# power_supply_v1.net
KiCad netlist of a schematic drawn in EAGLE
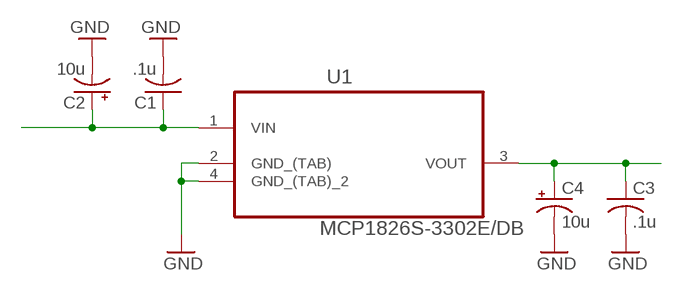
[diagram p0: schematic, sheet 1]
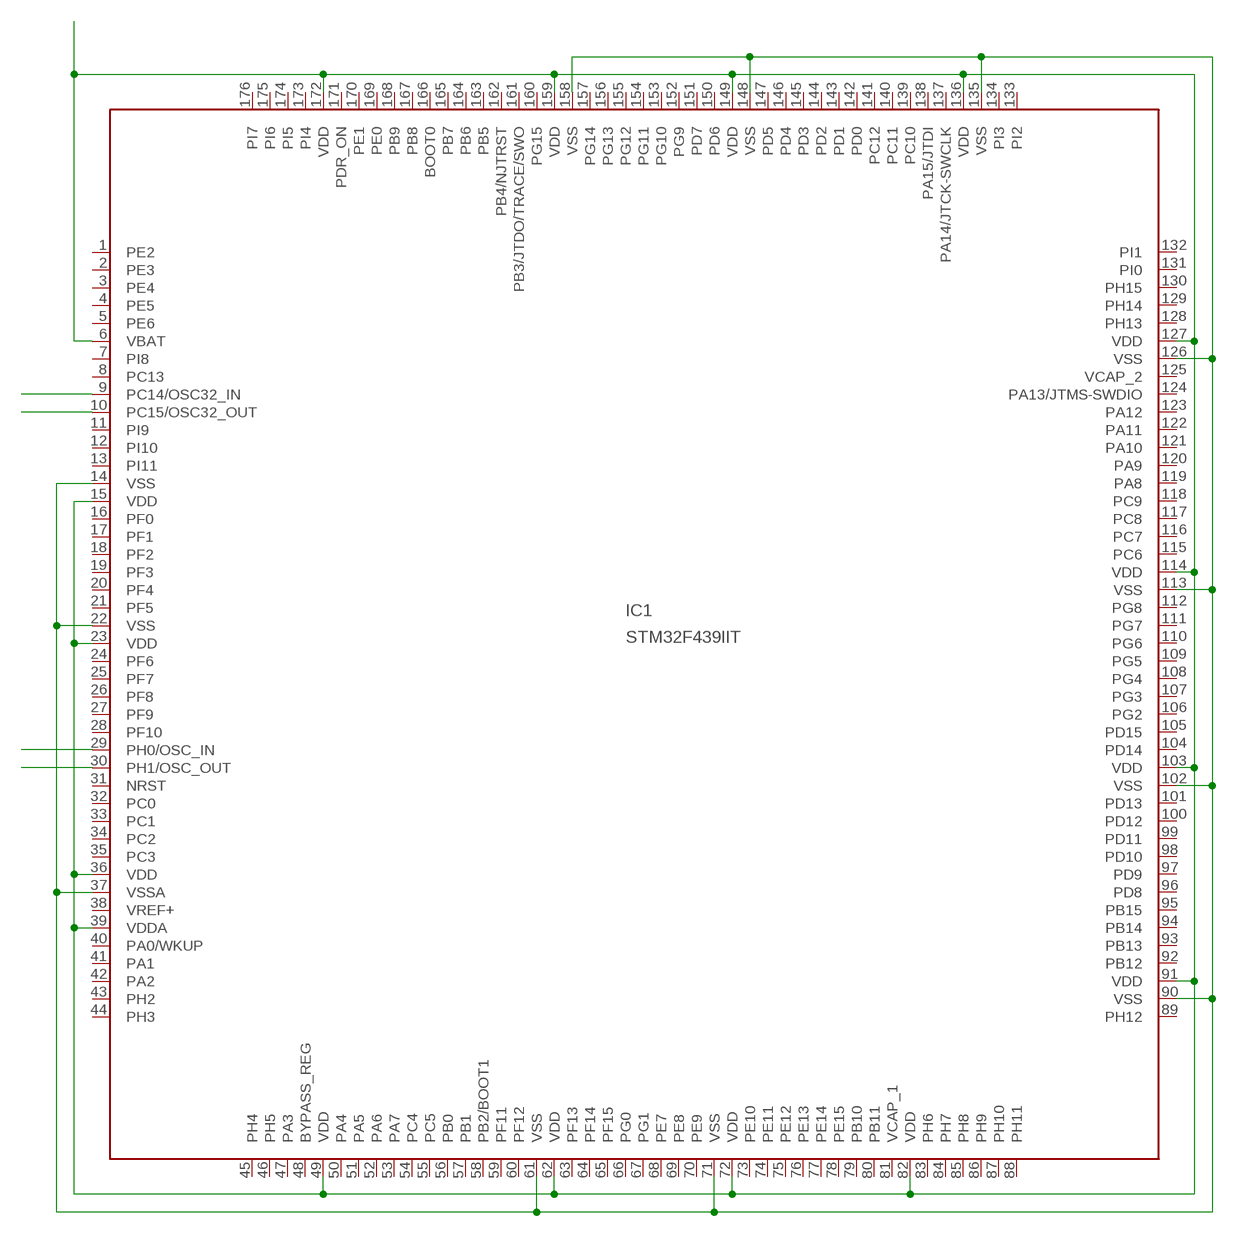
[diagram p1: schematic, sheet 2]

(export (version "E")
  (design (tool "Eeschema 10.0.6"))
  (components
    (comp (ref "C1")
      (value ".1u")
      (footprint "eagle-import:C0603")
      (libsource (lib "eagle-import") (part "C-USC0603"))
    )
    (comp (ref "C2")
      (value "10u")
      (footprint "eagle-import:D_7343-31W")
      (libsource (lib "eagle-import") (part "CPOL-USD/7343-31W"))
    )
    (comp (ref "C3")
      (value ".1u")
      (footprint "eagle-import:C0603")
      (libsource (lib "eagle-import") (part "C-USC0603"))
    )
    (comp (ref "C4")
      (value "10u")
      (footprint "eagle-import:D_7343-31W")
      (libsource (lib "eagle-import") (part "CPOL-USD/7343-31W"))
    )
    (comp (ref "U1")
      (value "MCP1826S-3302E/DB")
      (footprint "eagle-import:SOT230P700X180-4N")
      (libsource (lib "eagle-import") (part "MCP1826S-3302E/DB"))
    )
    (comp (ref "IC1")
      (value "STM32F439IIT")
      (footprint "eagle-import:LQFP-176")
      (libsource (lib "eagle-import") (part "STM32F439IIT"))
    )
  )
  (nets
    (net (code "1") (name "GND") (class "Default")
      (node (ref "C1") (pin "2") (pinfunction "2_2") (pintype "passive"))
      (node (ref "C2") (pin "-") (pinfunction "-_-") (pintype "passive"))
      (node (ref "C3") (pin "2") (pinfunction "2_2") (pintype "passive"))
      (node (ref "C4") (pin "-") (pinfunction "-_-") (pintype "passive"))
      (node (ref "U1") (pin "2") (pinfunction "GND_(TAB)_2") (pintype "passive"))
      (node (ref "U1") (pin "4") (pinfunction "GND_(TAB)_2_4") (pintype "passive"))
    )
    (net (code "2") (name "Net-(IC1-VBAT)") (class "Default")
      (node (ref "IC1") (pin "103") (pinfunction "VDD_103") (pintype "power_in"))
      (node (ref "IC1") (pin "114") (pinfunction "VDD_114") (pintype "power_in"))
      (node (ref "IC1") (pin "127") (pinfunction "VDD_127") (pintype "power_in"))
      (node (ref "IC1") (pin "136") (pinfunction "VDD_136") (pintype "power_in"))
      (node (ref "IC1") (pin "149") (pinfunction "VDD_149") (pintype "power_in"))
      (node (ref "IC1") (pin "15") (pinfunction "VDD_15") (pintype "power_in"))
      (node (ref "IC1") (pin "159") (pinfunction "VDD_159") (pintype "power_in"))
      (node (ref "IC1") (pin "172") (pinfunction "VDD_172") (pintype "power_in"))
      (node (ref "IC1") (pin "23") (pinfunction "VDD_23") (pintype "power_in"))
      (node (ref "IC1") (pin "36") (pinfunction "VDD_36") (pintype "power_in"))
      (node (ref "IC1") (pin "39") (pinfunction "VDDA_39") (pintype "power_in"))
      (node (ref "IC1") (pin "49") (pinfunction "VDD_49") (pintype "power_in"))
      (node (ref "IC1") (pin "6") (pinfunction "VBAT_6") (pintype "power_in"))
      (node (ref "IC1") (pin "62") (pinfunction "VDD_62") (pintype "bidirectional"))
      (node (ref "IC1") (pin "72") (pinfunction "VDD_72") (pintype "power_in"))
      (node (ref "IC1") (pin "82") (pinfunction "VDD_82") (pintype "power_in"))
      (node (ref "IC1") (pin "91") (pinfunction "VDD_91") (pintype "power_in"))
    )
    (net (code "3") (name "Net-(IC1-VSSA)") (class "Default")
      (node (ref "IC1") (pin "102") (pinfunction "VSS_102") (pintype "power_in"))
      (node (ref "IC1") (pin "113") (pinfunction "VSS_113") (pintype "power_in"))
      (node (ref "IC1") (pin "126") (pinfunction "VSS_126") (pintype "power_in"))
      (node (ref "IC1") (pin "135") (pinfunction "VSS_135") (pintype "power_in"))
      (node (ref "IC1") (pin "14") (pinfunction "VSS_14") (pintype "power_in"))
      (node (ref "IC1") (pin "148") (pinfunction "VSS_148") (pintype "power_in"))
      (node (ref "IC1") (pin "158") (pinfunction "VSS_158") (pintype "power_in"))
      (node (ref "IC1") (pin "22") (pinfunction "VSS_22") (pintype "power_in"))
      (node (ref "IC1") (pin "37") (pinfunction "VSSA_37") (pintype "power_in"))
      (node (ref "IC1") (pin "61") (pinfunction "VSS_61") (pintype "power_in"))
      (node (ref "IC1") (pin "71") (pinfunction "VSS_71") (pintype "power_in"))
      (node (ref "IC1") (pin "90") (pinfunction "VSS_90") (pintype "power_in"))
    )
    (net (code "4") (name "Net-(U1-VIN)") (class "Default")
      (node (ref "C1") (pin "1") (pinfunction "1_1") (pintype "passive"))
      (node (ref "C2") (pin "+") (pinfunction "+_+") (pintype "passive"))
      (node (ref "U1") (pin "1") (pinfunction "VIN_1") (pintype "input"))
    )
    (net (code "5") (name "Net-(U1-VOUT)") (class "Default")
      (node (ref "C3") (pin "1") (pinfunction "1_1") (pintype "passive"))
      (node (ref "C4") (pin "+") (pinfunction "+_+") (pintype "passive"))
      (node (ref "U1") (pin "3") (pinfunction "VOUT_3") (pintype "output"))
    )
    (net (code "6") (name "PDR_ON") (class "Default")
      (node (ref "IC1") (pin "171") (pinfunction "PDR_ON_171") (pintype "power_in"))
    )
    (net (code "7") (name "VCAP_1") (class "Default")
      (node (ref "IC1") (pin "81") (pinfunction "VCAP_1_81") (pintype "power_in"))
    )
    (net (code "8") (name "VCAP_2") (class "Default")
      (node (ref "IC1") (pin "125") (pinfunction "VCAP_2_125") (pintype "power_in"))
    )
    (net (code "9") (name "VREF+") (class "Default")
      (node (ref "IC1") (pin "38") (pinfunction "VREF+_38") (pintype "power_in"))
    )
    (net (code "10") (name "unconnected-(IC1-BOOT0-Pad166)") (class "Default")
      (node (ref "IC1") (pin "166") (pinfunction "BOOT0_166") (pintype "input"))
    )
    (net (code "11") (name "unconnected-(IC1-BYPASS_REG-Pad48)") (class "Default")
      (node (ref "IC1") (pin "48") (pinfunction "BYPASS_REG_48") (pintype "input"))
    )
    (net (code "12") (name "unconnected-(IC1-NRST-Pad31)") (class "Default")
      (node (ref "IC1") (pin "31") (pinfunction "NRST_31") (pintype "bidirectional"))
    )
    (net (code "13") (name "unconnected-(IC1-PA0{slash}WKUP-Pad40)") (class "Default")
      (node (ref "IC1") (pin "40") (pinfunction "PA0/WKUP_40") (pintype "bidirectional"))
    )
    (net (code "14") (name "unconnected-(IC1-PA1-Pad41)") (class "Default")
      (node (ref "IC1") (pin "41") (pinfunction "PA1_41") (pintype "bidirectional"))
    )
    (net (code "15") (name "unconnected-(IC1-PA2-Pad42)") (class "Default")
      (node (ref "IC1") (pin "42") (pinfunction "PA2_42") (pintype "bidirectional"))
    )
    (net (code "16") (name "unconnected-(IC1-PA3-Pad47)") (class "Default")
      (node (ref "IC1") (pin "47") (pinfunction "PA3_47") (pintype "bidirectional"))
    )
    (net (code "17") (name "unconnected-(IC1-PA4-Pad50)") (class "Default")
      (node (ref "IC1") (pin "50") (pinfunction "PA4_50") (pintype "bidirectional"))
    )
    (net (code "18") (name "unconnected-(IC1-PA5-Pad51)") (class "Default")
      (node (ref "IC1") (pin "51") (pinfunction "PA5_51") (pintype "bidirectional"))
    )
    (net (code "19") (name "unconnected-(IC1-PA6-Pad52)") (class "Default")
      (node (ref "IC1") (pin "52") (pinfunction "PA6_52") (pintype "bidirectional"))
    )
    (net (code "20") (name "unconnected-(IC1-PA7-Pad53)") (class "Default")
      (node (ref "IC1") (pin "53") (pinfunction "PA7_53") (pintype "bidirectional"))
    )
    (net (code "21") (name "unconnected-(IC1-PA8-Pad119)") (class "Default")
      (node (ref "IC1") (pin "119") (pinfunction "PA8_119") (pintype "bidirectional"))
    )
    (net (code "22") (name "unconnected-(IC1-PA9-Pad120)") (class "Default")
      (node (ref "IC1") (pin "120") (pinfunction "PA9_120") (pintype "bidirectional"))
    )
    (net (code "23") (name "unconnected-(IC1-PA10-Pad121)") (class "Default")
      (node (ref "IC1") (pin "121") (pinfunction "PA10_121") (pintype "bidirectional"))
    )
    (net (code "24") (name "unconnected-(IC1-PA11-Pad122)") (class "Default")
      (node (ref "IC1") (pin "122") (pinfunction "PA11_122") (pintype "bidirectional"))
    )
    (net (code "25") (name "unconnected-(IC1-PA12-Pad123)") (class "Default")
      (node (ref "IC1") (pin "123") (pinfunction "PA12_123") (pintype "bidirectional"))
    )
    (net (code "26") (name "unconnected-(IC1-PA13{slash}JTMS-SWDIO-Pad124)") (class "Default")
      (node (ref "IC1") (pin "124") (pinfunction "PA13/JTMS-SWDIO_124") (pintype "bidirectional"))
    )
    (net (code "27") (name "unconnected-(IC1-PA14{slash}JTCK-SWCLK-Pad137)") (class "Default")
      (node (ref "IC1") (pin "137") (pinfunction "PA14/JTCK-SWCLK_137") (pintype "bidirectional"))
    )
    (net (code "28") (name "unconnected-(IC1-PA15{slash}JTDI-Pad138)") (class "Default")
      (node (ref "IC1") (pin "138") (pinfunction "PA15/JTDI_138") (pintype "bidirectional"))
    )
    (net (code "29") (name "unconnected-(IC1-PB0-Pad56)") (class "Default")
      (node (ref "IC1") (pin "56") (pinfunction "PB0_56") (pintype "bidirectional"))
    )
    (net (code "30") (name "unconnected-(IC1-PB1-Pad57)") (class "Default")
      (node (ref "IC1") (pin "57") (pinfunction "PB1_57") (pintype "bidirectional"))
    )
    (net (code "31") (name "unconnected-(IC1-PB2{slash}BOOT1-Pad58)") (class "Default")
      (node (ref "IC1") (pin "58") (pinfunction "PB2/BOOT1_58") (pintype "bidirectional"))
    )
    (net (code "32") (name "unconnected-(IC1-PB3{slash}JTDO{slash}TRACE{slash}SWO-Pad161)") (class "Default")
      (node (ref "IC1") (pin "161") (pinfunction "PB3/JTDO/TRACE/SWO_161") (pintype "bidirectional"))
    )
    (net (code "33") (name "unconnected-(IC1-PB4{slash}NJTRST-Pad162)") (class "Default")
      (node (ref "IC1") (pin "162") (pinfunction "PB4/NJTRST_162") (pintype "bidirectional"))
    )
    (net (code "34") (name "unconnected-(IC1-PB5-Pad163)") (class "Default")
      (node (ref "IC1") (pin "163") (pinfunction "PB5_163") (pintype "bidirectional"))
    )
    (net (code "35") (name "unconnected-(IC1-PB6-Pad164)") (class "Default")
      (node (ref "IC1") (pin "164") (pinfunction "PB6_164") (pintype "bidirectional"))
    )
    (net (code "36") (name "unconnected-(IC1-PB7-Pad165)") (class "Default")
      (node (ref "IC1") (pin "165") (pinfunction "PB7_165") (pintype "bidirectional"))
    )
    (net (code "37") (name "unconnected-(IC1-PB8-Pad167)") (class "Default")
      (node (ref "IC1") (pin "167") (pinfunction "PB8_167") (pintype "bidirectional"))
    )
    (net (code "38") (name "unconnected-(IC1-PB9-Pad168)") (class "Default")
      (node (ref "IC1") (pin "168") (pinfunction "PB9_168") (pintype "bidirectional"))
    )
    (net (code "39") (name "unconnected-(IC1-PB10-Pad79)") (class "Default")
      (node (ref "IC1") (pin "79") (pinfunction "PB10_79") (pintype "bidirectional"))
    )
    (net (code "40") (name "unconnected-(IC1-PB11-Pad80)") (class "Default")
      (node (ref "IC1") (pin "80") (pinfunction "PB11_80") (pintype "bidirectional"))
    )
    (net (code "41") (name "unconnected-(IC1-PB12-Pad92)") (class "Default")
      (node (ref "IC1") (pin "92") (pinfunction "PB12_92") (pintype "bidirectional"))
    )
    (net (code "42") (name "unconnected-(IC1-PB13-Pad93)") (class "Default")
      (node (ref "IC1") (pin "93") (pinfunction "PB13_93") (pintype "bidirectional"))
    )
    (net (code "43") (name "unconnected-(IC1-PB14-Pad94)") (class "Default")
      (node (ref "IC1") (pin "94") (pinfunction "PB14_94") (pintype "bidirectional"))
    )
    (net (code "44") (name "unconnected-(IC1-PB15-Pad95)") (class "Default")
      (node (ref "IC1") (pin "95") (pinfunction "PB15_95") (pintype "bidirectional"))
    )
    (net (code "45") (name "unconnected-(IC1-PC0-Pad32)") (class "Default")
      (node (ref "IC1") (pin "32") (pinfunction "PC0_32") (pintype "bidirectional"))
    )
    (net (code "46") (name "unconnected-(IC1-PC1-Pad33)") (class "Default")
      (node (ref "IC1") (pin "33") (pinfunction "PC1_33") (pintype "bidirectional"))
    )
    (net (code "47") (name "unconnected-(IC1-PC2-Pad34)") (class "Default")
      (node (ref "IC1") (pin "34") (pinfunction "PC2_34") (pintype "bidirectional"))
    )
    (net (code "48") (name "unconnected-(IC1-PC3-Pad35)") (class "Default")
      (node (ref "IC1") (pin "35") (pinfunction "PC3_35") (pintype "bidirectional"))
    )
    (net (code "49") (name "unconnected-(IC1-PC4-Pad54)") (class "Default")
      (node (ref "IC1") (pin "54") (pinfunction "PC4_54") (pintype "bidirectional"))
    )
    (net (code "50") (name "unconnected-(IC1-PC5-Pad55)") (class "Default")
      (node (ref "IC1") (pin "55") (pinfunction "PC5_55") (pintype "bidirectional"))
    )
    (net (code "51") (name "unconnected-(IC1-PC6-Pad115)") (class "Default")
      (node (ref "IC1") (pin "115") (pinfunction "PC6_115") (pintype "bidirectional"))
    )
    (net (code "52") (name "unconnected-(IC1-PC7-Pad116)") (class "Default")
      (node (ref "IC1") (pin "116") (pinfunction "PC7_116") (pintype "bidirectional"))
    )
    (net (code "53") (name "unconnected-(IC1-PC8-Pad117)") (class "Default")
      (node (ref "IC1") (pin "117") (pinfunction "PC8_117") (pintype "bidirectional"))
    )
    (net (code "54") (name "unconnected-(IC1-PC9-Pad118)") (class "Default")
      (node (ref "IC1") (pin "118") (pinfunction "PC9_118") (pintype "bidirectional"))
    )
    (net (code "55") (name "unconnected-(IC1-PC10-Pad139)") (class "Default")
      (node (ref "IC1") (pin "139") (pinfunction "PC10_139") (pintype "bidirectional"))
    )
    (net (code "56") (name "unconnected-(IC1-PC11-Pad140)") (class "Default")
      (node (ref "IC1") (pin "140") (pinfunction "PC11_140") (pintype "bidirectional"))
    )
    (net (code "57") (name "unconnected-(IC1-PC12-Pad141)") (class "Default")
      (node (ref "IC1") (pin "141") (pinfunction "PC12_141") (pintype "bidirectional"))
    )
    (net (code "58") (name "unconnected-(IC1-PC13-Pad8)") (class "Default")
      (node (ref "IC1") (pin "8") (pinfunction "PC13_8") (pintype "bidirectional"))
    )
    (net (code "59") (name "unconnected-(IC1-PC14{slash}OSC32_IN-Pad9)") (class "Default")
      (node (ref "IC1") (pin "9") (pinfunction "PC14/OSC32_IN_9") (pintype "bidirectional"))
    )
    (net (code "60") (name "unconnected-(IC1-PC15{slash}OSC32_OUT-Pad10)") (class "Default")
      (node (ref "IC1") (pin "10") (pinfunction "PC15/OSC32_OUT_10") (pintype "bidirectional"))
    )
    (net (code "61") (name "unconnected-(IC1-PD0-Pad142)") (class "Default")
      (node (ref "IC1") (pin "142") (pinfunction "PD0_142") (pintype "bidirectional"))
    )
    (net (code "62") (name "unconnected-(IC1-PD1-Pad143)") (class "Default")
      (node (ref "IC1") (pin "143") (pinfunction "PD1_143") (pintype "bidirectional"))
    )
    (net (code "63") (name "unconnected-(IC1-PD2-Pad144)") (class "Default")
      (node (ref "IC1") (pin "144") (pinfunction "PD2_144") (pintype "bidirectional"))
    )
    (net (code "64") (name "unconnected-(IC1-PD3-Pad145)") (class "Default")
      (node (ref "IC1") (pin "145") (pinfunction "PD3_145") (pintype "bidirectional"))
    )
    (net (code "65") (name "unconnected-(IC1-PD4-Pad146)") (class "Default")
      (node (ref "IC1") (pin "146") (pinfunction "PD4_146") (pintype "bidirectional"))
    )
    (net (code "66") (name "unconnected-(IC1-PD5-Pad147)") (class "Default")
      (node (ref "IC1") (pin "147") (pinfunction "PD5_147") (pintype "bidirectional"))
    )
    (net (code "67") (name "unconnected-(IC1-PD6-Pad150)") (class "Default")
      (node (ref "IC1") (pin "150") (pinfunction "PD6_150") (pintype "bidirectional"))
    )
    (net (code "68") (name "unconnected-(IC1-PD7-Pad151)") (class "Default")
      (node (ref "IC1") (pin "151") (pinfunction "PD7_151") (pintype "bidirectional"))
    )
    (net (code "69") (name "unconnected-(IC1-PD8-Pad96)") (class "Default")
      (node (ref "IC1") (pin "96") (pinfunction "PD8_96") (pintype "bidirectional"))
    )
    (net (code "70") (name "unconnected-(IC1-PD9-Pad97)") (class "Default")
      (node (ref "IC1") (pin "97") (pinfunction "PD9_97") (pintype "bidirectional"))
    )
    (net (code "71") (name "unconnected-(IC1-PD10-Pad98)") (class "Default")
      (node (ref "IC1") (pin "98") (pinfunction "PD10_98") (pintype "bidirectional"))
    )
    (net (code "72") (name "unconnected-(IC1-PD11-Pad99)") (class "Default")
      (node (ref "IC1") (pin "99") (pinfunction "PD11_99") (pintype "bidirectional"))
    )
    (net (code "73") (name "unconnected-(IC1-PD12-Pad100)") (class "Default")
      (node (ref "IC1") (pin "100") (pinfunction "PD12_100") (pintype "bidirectional"))
    )
    (net (code "74") (name "unconnected-(IC1-PD13-Pad101)") (class "Default")
      (node (ref "IC1") (pin "101") (pinfunction "PD13_101") (pintype "bidirectional"))
    )
    (net (code "75") (name "unconnected-(IC1-PD14-Pad104)") (class "Default")
      (node (ref "IC1") (pin "104") (pinfunction "PD14_104") (pintype "bidirectional"))
    )
    (net (code "76") (name "unconnected-(IC1-PD15-Pad105)") (class "Default")
      (node (ref "IC1") (pin "105") (pinfunction "PD15_105") (pintype "bidirectional"))
    )
    (net (code "77") (name "unconnected-(IC1-PE0-Pad169)") (class "Default")
      (node (ref "IC1") (pin "169") (pinfunction "PE0_169") (pintype "bidirectional"))
    )
    (net (code "78") (name "unconnected-(IC1-PE1-Pad170)") (class "Default")
      (node (ref "IC1") (pin "170") (pinfunction "PE1_170") (pintype "bidirectional"))
    )
    (net (code "79") (name "unconnected-(IC1-PE2-Pad1)") (class "Default")
      (node (ref "IC1") (pin "1") (pinfunction "PE2_1") (pintype "bidirectional"))
    )
    (net (code "80") (name "unconnected-(IC1-PE3-Pad2)") (class "Default")
      (node (ref "IC1") (pin "2") (pinfunction "PE3_2") (pintype "bidirectional"))
    )
    (net (code "81") (name "unconnected-(IC1-PE4-Pad3)") (class "Default")
      (node (ref "IC1") (pin "3") (pinfunction "PE4_3") (pintype "bidirectional"))
    )
    (net (code "82") (name "unconnected-(IC1-PE5-Pad4)") (class "Default")
      (node (ref "IC1") (pin "4") (pinfunction "PE5_4") (pintype "bidirectional"))
    )
    (net (code "83") (name "unconnected-(IC1-PE6-Pad5)") (class "Default")
      (node (ref "IC1") (pin "5") (pinfunction "PE6_5") (pintype "bidirectional"))
    )
    (net (code "84") (name "unconnected-(IC1-PE7-Pad68)") (class "Default")
      (node (ref "IC1") (pin "68") (pinfunction "PE7_68") (pintype "bidirectional"))
    )
    (net (code "85") (name "unconnected-(IC1-PE8-Pad69)") (class "Default")
      (node (ref "IC1") (pin "69") (pinfunction "PE8_69") (pintype "bidirectional"))
    )
    (net (code "86") (name "unconnected-(IC1-PE9-Pad70)") (class "Default")
      (node (ref "IC1") (pin "70") (pinfunction "PE9_70") (pintype "bidirectional"))
    )
    (net (code "87") (name "unconnected-(IC1-PE10-Pad73)") (class "Default")
      (node (ref "IC1") (pin "73") (pinfunction "PE10_73") (pintype "bidirectional"))
    )
    (net (code "88") (name "unconnected-(IC1-PE11-Pad74)") (class "Default")
      (node (ref "IC1") (pin "74") (pinfunction "PE11_74") (pintype "bidirectional"))
    )
    (net (code "89") (name "unconnected-(IC1-PE12-Pad75)") (class "Default")
      (node (ref "IC1") (pin "75") (pinfunction "PE12_75") (pintype "bidirectional"))
    )
    (net (code "90") (name "unconnected-(IC1-PE13-Pad76)") (class "Default")
      (node (ref "IC1") (pin "76") (pinfunction "PE13_76") (pintype "bidirectional"))
    )
    (net (code "91") (name "unconnected-(IC1-PE14-Pad77)") (class "Default")
      (node (ref "IC1") (pin "77") (pinfunction "PE14_77") (pintype "bidirectional"))
    )
    (net (code "92") (name "unconnected-(IC1-PE15-Pad78)") (class "Default")
      (node (ref "IC1") (pin "78") (pinfunction "PE15_78") (pintype "bidirectional"))
    )
    (net (code "93") (name "unconnected-(IC1-PF0-Pad16)") (class "Default")
      (node (ref "IC1") (pin "16") (pinfunction "PF0_16") (pintype "bidirectional"))
    )
    (net (code "94") (name "unconnected-(IC1-PF1-Pad17)") (class "Default")
      (node (ref "IC1") (pin "17") (pinfunction "PF1_17") (pintype "bidirectional"))
    )
    (net (code "95") (name "unconnected-(IC1-PF2-Pad18)") (class "Default")
      (node (ref "IC1") (pin "18") (pinfunction "PF2_18") (pintype "bidirectional"))
    )
    (net (code "96") (name "unconnected-(IC1-PF3-Pad19)") (class "Default")
      (node (ref "IC1") (pin "19") (pinfunction "PF3_19") (pintype "bidirectional"))
    )
    (net (code "97") (name "unconnected-(IC1-PF4-Pad20)") (class "Default")
      (node (ref "IC1") (pin "20") (pinfunction "PF4_20") (pintype "bidirectional"))
    )
    (net (code "98") (name "unconnected-(IC1-PF5-Pad21)") (class "Default")
      (node (ref "IC1") (pin "21") (pinfunction "PF5_21") (pintype "bidirectional"))
    )
    (net (code "99") (name "unconnected-(IC1-PF6-Pad24)") (class "Default")
      (node (ref "IC1") (pin "24") (pinfunction "PF6_24") (pintype "bidirectional"))
    )
    (net (code "100") (name "unconnected-(IC1-PF7-Pad25)") (class "Default")
      (node (ref "IC1") (pin "25") (pinfunction "PF7_25") (pintype "bidirectional"))
    )
    (net (code "101") (name "unconnected-(IC1-PF8-Pad26)") (class "Default")
      (node (ref "IC1") (pin "26") (pinfunction "PF8_26") (pintype "bidirectional"))
    )
    (net (code "102") (name "unconnected-(IC1-PF9-Pad27)") (class "Default")
      (node (ref "IC1") (pin "27") (pinfunction "PF9_27") (pintype "bidirectional"))
    )
    (net (code "103") (name "unconnected-(IC1-PF10-Pad28)") (class "Default")
      (node (ref "IC1") (pin "28") (pinfunction "PF10_28") (pintype "bidirectional"))
    )
    (net (code "104") (name "unconnected-(IC1-PF11-Pad59)") (class "Default")
      (node (ref "IC1") (pin "59") (pinfunction "PF11_59") (pintype "bidirectional"))
    )
    (net (code "105") (name "unconnected-(IC1-PF12-Pad60)") (class "Default")
      (node (ref "IC1") (pin "60") (pinfunction "PF12_60") (pintype "bidirectional"))
    )
    (net (code "106") (name "unconnected-(IC1-PF13-Pad63)") (class "Default")
      (node (ref "IC1") (pin "63") (pinfunction "PF13_63") (pintype "bidirectional"))
    )
    (net (code "107") (name "unconnected-(IC1-PF14-Pad64)") (class "Default")
      (node (ref "IC1") (pin "64") (pinfunction "PF14_64") (pintype "bidirectional"))
    )
    (net (code "108") (name "unconnected-(IC1-PF15-Pad65)") (class "Default")
      (node (ref "IC1") (pin "65") (pinfunction "PF15_65") (pintype "bidirectional"))
    )
    (net (code "109") (name "unconnected-(IC1-PG0-Pad66)") (class "Default")
      (node (ref "IC1") (pin "66") (pinfunction "PG0_66") (pintype "bidirectional"))
    )
    (net (code "110") (name "unconnected-(IC1-PG1-Pad67)") (class "Default")
      (node (ref "IC1") (pin "67") (pinfunction "PG1_67") (pintype "bidirectional"))
    )
    (net (code "111") (name "unconnected-(IC1-PG2-Pad106)") (class "Default")
      (node (ref "IC1") (pin "106") (pinfunction "PG2_106") (pintype "bidirectional"))
    )
    (net (code "112") (name "unconnected-(IC1-PG3-Pad107)") (class "Default")
      (node (ref "IC1") (pin "107") (pinfunction "PG3_107") (pintype "bidirectional"))
    )
    (net (code "113") (name "unconnected-(IC1-PG4-Pad108)") (class "Default")
      (node (ref "IC1") (pin "108") (pinfunction "PG4_108") (pintype "bidirectional"))
    )
    (net (code "114") (name "unconnected-(IC1-PG5-Pad109)") (class "Default")
      (node (ref "IC1") (pin "109") (pinfunction "PG5_109") (pintype "bidirectional"))
    )
    (net (code "115") (name "unconnected-(IC1-PG6-Pad110)") (class "Default")
      (node (ref "IC1") (pin "110") (pinfunction "PG6_110") (pintype "bidirectional"))
    )
    (net (code "116") (name "unconnected-(IC1-PG7-Pad111)") (class "Default")
      (node (ref "IC1") (pin "111") (pinfunction "PG7_111") (pintype "bidirectional"))
    )
    (net (code "117") (name "unconnected-(IC1-PG8-Pad112)") (class "Default")
      (node (ref "IC1") (pin "112") (pinfunction "PG8_112") (pintype "bidirectional"))
    )
    (net (code "118") (name "unconnected-(IC1-PG9-Pad152)") (class "Default")
      (node (ref "IC1") (pin "152") (pinfunction "PG9_152") (pintype "bidirectional"))
    )
    (net (code "119") (name "unconnected-(IC1-PG10-Pad153)") (class "Default")
      (node (ref "IC1") (pin "153") (pinfunction "PG10_153") (pintype "bidirectional"))
    )
    (net (code "120") (name "unconnected-(IC1-PG11-Pad154)") (class "Default")
      (node (ref "IC1") (pin "154") (pinfunction "PG11_154") (pintype "bidirectional"))
    )
    (net (code "121") (name "unconnected-(IC1-PG12-Pad155)") (class "Default")
      (node (ref "IC1") (pin "155") (pinfunction "PG12_155") (pintype "bidirectional"))
    )
    (net (code "122") (name "unconnected-(IC1-PG13-Pad156)") (class "Default")
      (node (ref "IC1") (pin "156") (pinfunction "PG13_156") (pintype "bidirectional"))
    )
    (net (code "123") (name "unconnected-(IC1-PG14-Pad157)") (class "Default")
      (node (ref "IC1") (pin "157") (pinfunction "PG14_157") (pintype "bidirectional"))
    )
    (net (code "124") (name "unconnected-(IC1-PG15-Pad160)") (class "Default")
      (node (ref "IC1") (pin "160") (pinfunction "PG15_160") (pintype "bidirectional"))
    )
    (net (code "125") (name "unconnected-(IC1-PH0{slash}OSC_IN-Pad29)") (class "Default")
      (node (ref "IC1") (pin "29") (pinfunction "PH0/OSC_IN_29") (pintype "bidirectional"))
    )
    (net (code "126") (name "unconnected-(IC1-PH1{slash}OSC_OUT-Pad30)") (class "Default")
      (node (ref "IC1") (pin "30") (pinfunction "PH1/OSC_OUT_30") (pintype "bidirectional"))
    )
    (net (code "127") (name "unconnected-(IC1-PH2-Pad43)") (class "Default")
      (node (ref "IC1") (pin "43") (pinfunction "PH2_43") (pintype "bidirectional"))
    )
    (net (code "128") (name "unconnected-(IC1-PH3-Pad44)") (class "Default")
      (node (ref "IC1") (pin "44") (pinfunction "PH3_44") (pintype "bidirectional"))
    )
    (net (code "129") (name "unconnected-(IC1-PH4-Pad45)") (class "Default")
      (node (ref "IC1") (pin "45") (pinfunction "PH4_45") (pintype "bidirectional"))
    )
    (net (code "130") (name "unconnected-(IC1-PH5-Pad46)") (class "Default")
      (node (ref "IC1") (pin "46") (pinfunction "PH5_46") (pintype "bidirectional"))
    )
    (net (code "131") (name "unconnected-(IC1-PH6-Pad83)") (class "Default")
      (node (ref "IC1") (pin "83") (pinfunction "PH6_83") (pintype "bidirectional"))
    )
    (net (code "132") (name "unconnected-(IC1-PH7-Pad84)") (class "Default")
      (node (ref "IC1") (pin "84") (pinfunction "PH7_84") (pintype "bidirectional"))
    )
    (net (code "133") (name "unconnected-(IC1-PH8-Pad85)") (class "Default")
      (node (ref "IC1") (pin "85") (pinfunction "PH8_85") (pintype "bidirectional"))
    )
    (net (code "134") (name "unconnected-(IC1-PH9-Pad86)") (class "Default")
      (node (ref "IC1") (pin "86") (pinfunction "PH9_86") (pintype "bidirectional"))
    )
    (net (code "135") (name "unconnected-(IC1-PH10-Pad87)") (class "Default")
      (node (ref "IC1") (pin "87") (pinfunction "PH10_87") (pintype "bidirectional"))
    )
    (net (code "136") (name "unconnected-(IC1-PH11-Pad88)") (class "Default")
      (node (ref "IC1") (pin "88") (pinfunction "PH11_88") (pintype "bidirectional"))
    )
    (net (code "137") (name "unconnected-(IC1-PH12-Pad89)") (class "Default")
      (node (ref "IC1") (pin "89") (pinfunction "PH12_89") (pintype "bidirectional"))
    )
    (net (code "138") (name "unconnected-(IC1-PH13-Pad128)") (class "Default")
      (node (ref "IC1") (pin "128") (pinfunction "PH13_128") (pintype "bidirectional"))
    )
    (net (code "139") (name "unconnected-(IC1-PH14-Pad129)") (class "Default")
      (node (ref "IC1") (pin "129") (pinfunction "PH14_129") (pintype "bidirectional"))
    )
    (net (code "140") (name "unconnected-(IC1-PH15-Pad130)") (class "Default")
      (node (ref "IC1") (pin "130") (pinfunction "PH15_130") (pintype "bidirectional"))
    )
    (net (code "141") (name "unconnected-(IC1-PI0-Pad131)") (class "Default")
      (node (ref "IC1") (pin "131") (pinfunction "PI0_131") (pintype "bidirectional"))
    )
    (net (code "142") (name "unconnected-(IC1-PI1-Pad132)") (class "Default")
      (node (ref "IC1") (pin "132") (pinfunction "PI1_132") (pintype "bidirectional"))
    )
    (net (code "143") (name "unconnected-(IC1-PI2-Pad133)") (class "Default")
      (node (ref "IC1") (pin "133") (pinfunction "PI2_133") (pintype "bidirectional"))
    )
    (net (code "144") (name "unconnected-(IC1-PI3-Pad134)") (class "Default")
      (node (ref "IC1") (pin "134") (pinfunction "PI3_134") (pintype "bidirectional"))
    )
    (net (code "145") (name "unconnected-(IC1-PI4-Pad173)") (class "Default")
      (node (ref "IC1") (pin "173") (pinfunction "PI4_173") (pintype "bidirectional"))
    )
    (net (code "146") (name "unconnected-(IC1-PI5-Pad174)") (class "Default")
      (node (ref "IC1") (pin "174") (pinfunction "PI5_174") (pintype "bidirectional"))
    )
    (net (code "147") (name "unconnected-(IC1-PI6-Pad175)") (class "Default")
      (node (ref "IC1") (pin "175") (pinfunction "PI6_175") (pintype "bidirectional"))
    )
    (net (code "148") (name "unconnected-(IC1-PI7-Pad176)") (class "Default")
      (node (ref "IC1") (pin "176") (pinfunction "PI7_176") (pintype "bidirectional"))
    )
    (net (code "149") (name "unconnected-(IC1-PI8-Pad7)") (class "Default")
      (node (ref "IC1") (pin "7") (pinfunction "PI8_7") (pintype "bidirectional"))
    )
    (net (code "150") (name "unconnected-(IC1-PI9-Pad11)") (class "Default")
      (node (ref "IC1") (pin "11") (pinfunction "PI9_11") (pintype "bidirectional"))
    )
    (net (code "151") (name "unconnected-(IC1-PI10-Pad12)") (class "Default")
      (node (ref "IC1") (pin "12") (pinfunction "PI10_12") (pintype "bidirectional"))
    )
    (net (code "152") (name "unconnected-(IC1-PI11-Pad13)") (class "Default")
      (node (ref "IC1") (pin "13") (pinfunction "PI11_13") (pintype "bidirectional"))
    )
  )
)
